# 2513_Replacement.net
KiCad netlist of a schematic drawn in EasyEDA
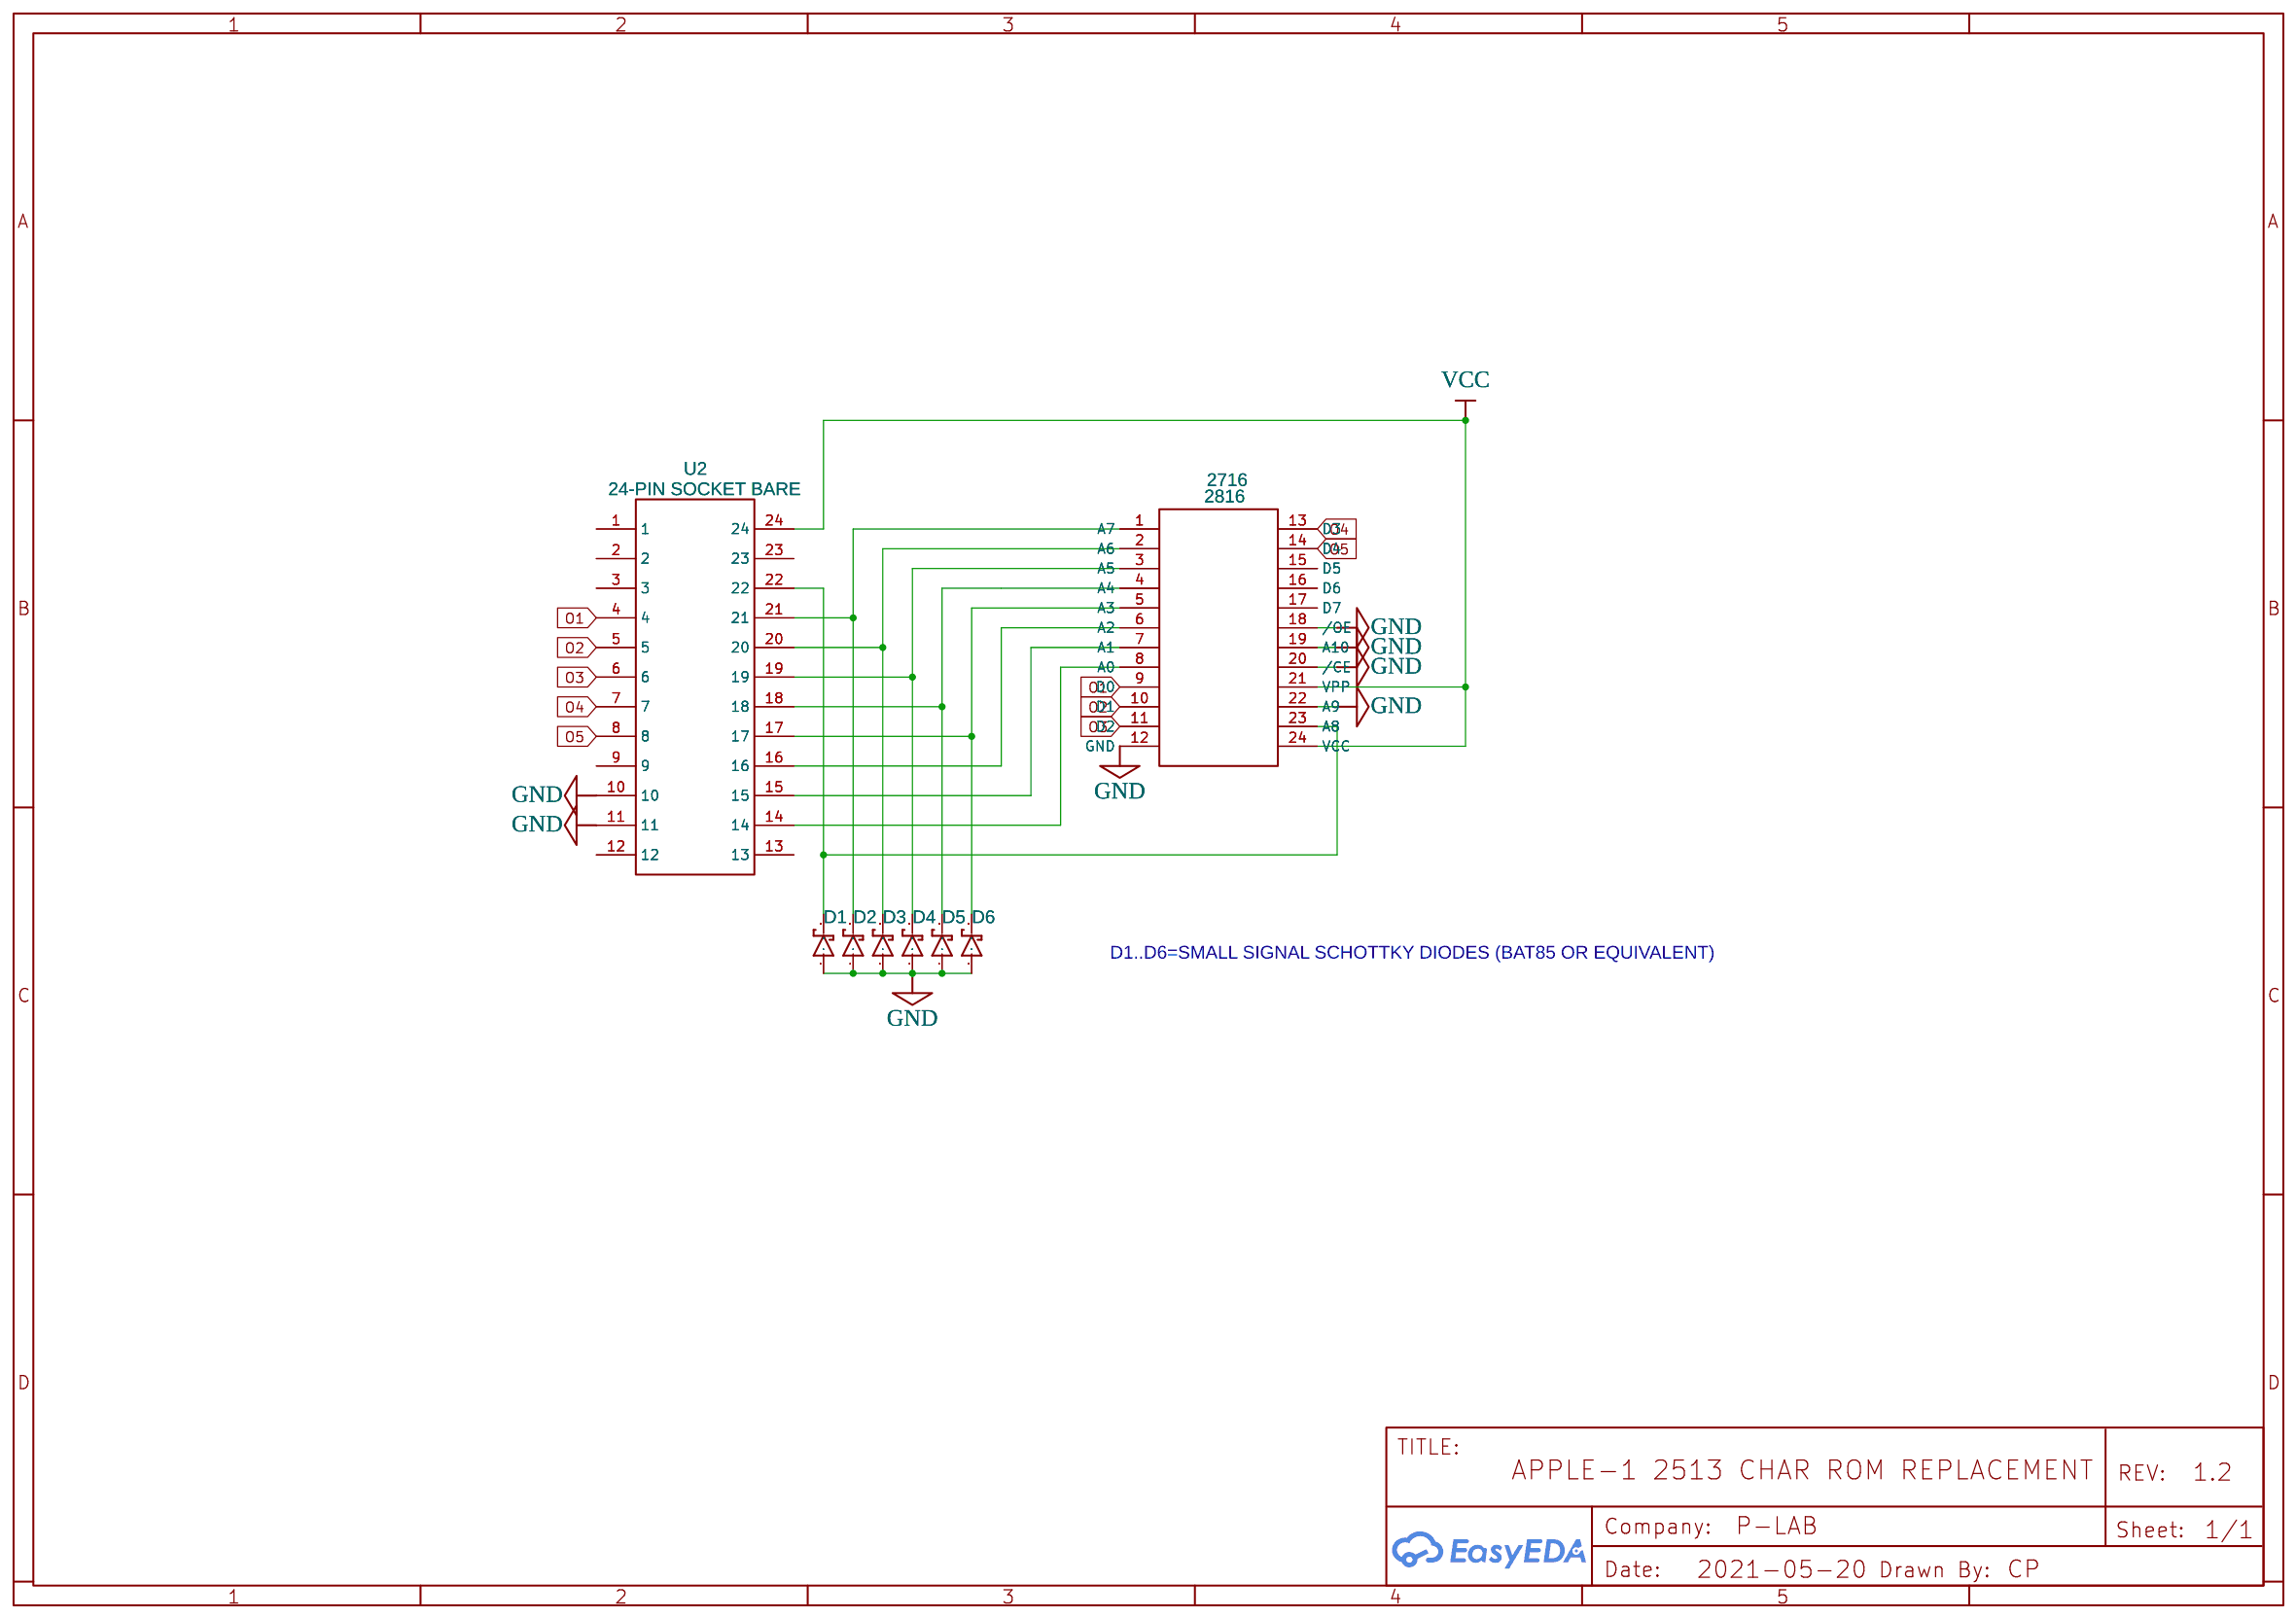
[diagram p0: schematic sheet]

(export (version "E")
  (design (tool "Eeschema 10.0.6"))
  (components
    (comp (ref "2716")
      (value "2816")
      (fields (field (name "BOM_Manufacturer Part") "27C16"))
      (libsource (lib "") (part "2716"))
    )
    (comp (ref "D1") (value "SCHOTTKY") (libsource (lib "") (part "SCHOTTKY")))
    (comp (ref "D2") (value "SCHOTTKY") (libsource (lib "") (part "SCHOTTKY")))
    (comp (ref "D3") (value "SCHOTTKY") (libsource (lib "") (part "SCHOTTKY")))
    (comp (ref "D4") (value "SCHOTTKY") (libsource (lib "") (part "SCHOTTKY")))
    (comp (ref "D5") (value "SCHOTTKY") (libsource (lib "") (part "SCHOTTKY")))
    (comp (ref "D6") (value "SCHOTTKY") (libsource (lib "") (part "SCHOTTKY")))
    (comp (ref "U2") (value "24-PIN SOCKET BARE") (libsource (lib "") (part "24-PIN SOCKET BARE")))
  )
  (nets
    (net (code "1") (name "GND") (class "Default")
      (node (ref "2716") (pin "12") (pinfunction "GND_12") (pintype "unspecified"))
      (node (ref "2716") (pin "18") (pinfunction "/OE_18") (pintype "unspecified"))
      (node (ref "2716") (pin "19") (pinfunction "A10_19") (pintype "unspecified"))
      (node (ref "2716") (pin "20") (pinfunction "/CE_20") (pintype "unspecified"))
      (node (ref "2716") (pin "22") (pinfunction "A9_22") (pintype "unspecified"))
      (node (ref "D1") (pin "A") (pinfunction "A_A") (pintype "bidirectional"))
      (node (ref "D2") (pin "A") (pinfunction "A_A") (pintype "bidirectional"))
      (node (ref "D3") (pin "A") (pinfunction "A_A") (pintype "bidirectional"))
      (node (ref "D4") (pin "A") (pinfunction "A_A") (pintype "bidirectional"))
      (node (ref "D5") (pin "A") (pinfunction "A_A") (pintype "bidirectional"))
      (node (ref "D6") (pin "A") (pinfunction "A_A") (pintype "bidirectional"))
      (node (ref "U2") (pin "10") (pinfunction "10_10") (pintype "unspecified"))
      (node (ref "U2") (pin "11") (pinfunction "11_11") (pintype "unspecified"))
    )
    (net (code "2") (name "Net-(2716-A0)") (class "Default")
      (node (ref "2716") (pin "8") (pinfunction "A0_8") (pintype "unspecified"))
      (node (ref "U2") (pin "14") (pinfunction "14_14") (pintype "unspecified"))
    )
    (net (code "3") (name "Net-(2716-A1)") (class "Default")
      (node (ref "2716") (pin "7") (pinfunction "A1_7") (pintype "unspecified"))
      (node (ref "U2") (pin "15") (pinfunction "15_15") (pintype "unspecified"))
    )
    (net (code "4") (name "Net-(2716-A2)") (class "Default")
      (node (ref "2716") (pin "6") (pinfunction "A2_6") (pintype "unspecified"))
      (node (ref "U2") (pin "16") (pinfunction "16_16") (pintype "unspecified"))
    )
    (net (code "5") (name "Net-(2716-A3)") (class "Default")
      (node (ref "2716") (pin "5") (pinfunction "A3_5") (pintype "unspecified"))
      (node (ref "D6") (pin "C") (pinfunction "C_C") (pintype "bidirectional"))
      (node (ref "U2") (pin "17") (pinfunction "17_17") (pintype "unspecified"))
    )
    (net (code "6") (name "Net-(2716-A4)") (class "Default")
      (node (ref "2716") (pin "4") (pinfunction "A4_4") (pintype "unspecified"))
      (node (ref "D5") (pin "C") (pinfunction "C_C") (pintype "bidirectional"))
      (node (ref "U2") (pin "18") (pinfunction "18_18") (pintype "bidirectional"))
    )
    (net (code "7") (name "Net-(2716-A5)") (class "Default")
      (node (ref "2716") (pin "3") (pinfunction "A5_3") (pintype "unspecified"))
      (node (ref "D4") (pin "C") (pinfunction "C_C") (pintype "bidirectional"))
      (node (ref "U2") (pin "19") (pinfunction "19_19") (pintype "bidirectional"))
    )
    (net (code "8") (name "Net-(2716-A6)") (class "Default")
      (node (ref "2716") (pin "2") (pinfunction "A6_2") (pintype "unspecified"))
      (node (ref "D3") (pin "C") (pinfunction "C_C") (pintype "bidirectional"))
      (node (ref "U2") (pin "20") (pinfunction "20_20") (pintype "bidirectional"))
    )
    (net (code "9") (name "Net-(2716-A7)") (class "Default")
      (node (ref "2716") (pin "1") (pinfunction "A7_1") (pintype "unspecified"))
      (node (ref "D2") (pin "C") (pinfunction "C_C") (pintype "bidirectional"))
      (node (ref "U2") (pin "21") (pinfunction "21_21") (pintype "bidirectional"))
    )
    (net (code "10") (name "Net-(2716-A8)") (class "Default")
      (node (ref "2716") (pin "23") (pinfunction "A8_23") (pintype "unspecified"))
      (node (ref "D1") (pin "C") (pinfunction "C_C") (pintype "bidirectional"))
      (node (ref "U2") (pin "22") (pinfunction "22_22") (pintype "bidirectional"))
    )
    (net (code "11") (name "O1") (class "Default")
      (node (ref "2716") (pin "9") (pinfunction "D0_9") (pintype "unspecified"))
      (node (ref "U2") (pin "4") (pinfunction "4_4") (pintype "unspecified"))
    )
    (net (code "12") (name "O2") (class "Default")
      (node (ref "2716") (pin "10") (pinfunction "D1_10") (pintype "unspecified"))
      (node (ref "U2") (pin "5") (pinfunction "5_5") (pintype "unspecified"))
    )
    (net (code "13") (name "O3") (class "Default")
      (node (ref "2716") (pin "11") (pinfunction "D2_11") (pintype "unspecified"))
      (node (ref "U2") (pin "6") (pinfunction "6_6") (pintype "unspecified"))
    )
    (net (code "14") (name "O4") (class "Default")
      (node (ref "2716") (pin "13") (pinfunction "D3_13") (pintype "unspecified"))
      (node (ref "U2") (pin "7") (pinfunction "7_7") (pintype "unspecified"))
    )
    (net (code "15") (name "O5") (class "Default")
      (node (ref "2716") (pin "14") (pinfunction "D4_14") (pintype "unspecified"))
      (node (ref "U2") (pin "8") (pinfunction "8_8") (pintype "unspecified"))
    )
    (net (code "16") (name "VCC") (class "Default")
      (node (ref "2716") (pin "21") (pinfunction "VPP_21") (pintype "unspecified"))
      (node (ref "2716") (pin "24") (pinfunction "VCC_24") (pintype "unspecified"))
      (node (ref "U2") (pin "24") (pinfunction "24_24") (pintype "passive"))
    )
    (net (code "17") (name "unconnected-(2716-D5-Pad15)") (class "Default")
      (node (ref "2716") (pin "15") (pinfunction "D5_15") (pintype "unspecified"))
    )
    (net (code "18") (name "unconnected-(2716-D6-Pad16)") (class "Default")
      (node (ref "2716") (pin "16") (pinfunction "D6_16") (pintype "unspecified"))
    )
    (net (code "19") (name "unconnected-(2716-D7-Pad17)") (class "Default")
      (node (ref "2716") (pin "17") (pinfunction "D7_17") (pintype "unspecified"))
    )
    (net (code "20") (name "unconnected-(U2-Pad1)") (class "Default")
      (node (ref "U2") (pin "1") (pinfunction "1_1") (pintype "unspecified"))
    )
    (net (code "21") (name "unconnected-(U2-Pad2)") (class "Default")
      (node (ref "U2") (pin "2") (pinfunction "2_2") (pintype "unspecified"))
    )
    (net (code "22") (name "unconnected-(U2-Pad3)") (class "Default")
      (node (ref "U2") (pin "3") (pinfunction "3_3") (pintype "unspecified"))
    )
    (net (code "23") (name "unconnected-(U2-Pad9)") (class "Default")
      (node (ref "U2") (pin "9") (pinfunction "9_9") (pintype "unspecified"))
    )
    (net (code "24") (name "unconnected-(U2-Pad12)") (class "Default")
      (node (ref "U2") (pin "12") (pinfunction "12_12") (pintype "passive"))
    )
    (net (code "25") (name "unconnected-(U2-Pad13)") (class "Default")
      (node (ref "U2") (pin "13") (pinfunction "13_13") (pintype "unspecified"))
    )
    (net (code "26") (name "unconnected-(U2-Pad23)") (class "Default")
      (node (ref "U2") (pin "23") (pinfunction "23_23") (pintype "bidirectional"))
    )
  )
)
